# Connector.net
KiCad netlist of a schematic drawn in Altium Designer
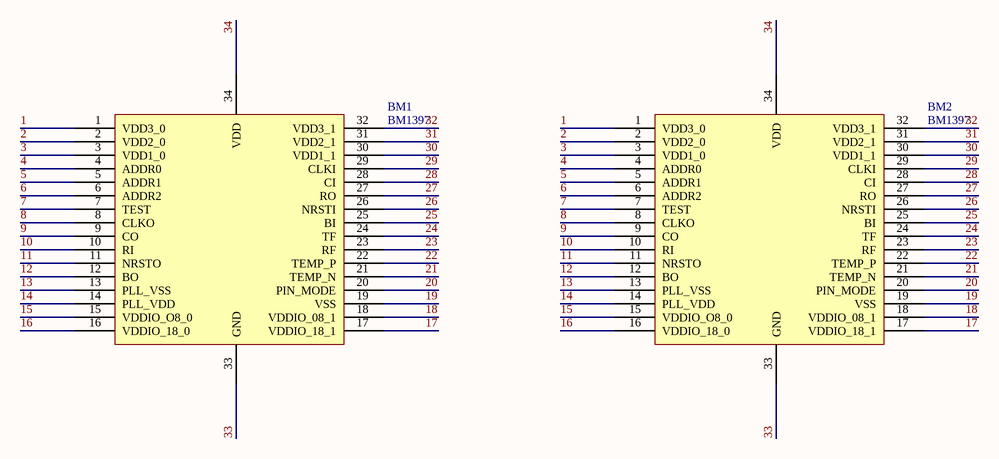
[diagram p0: Connector.SchDoc]

(export (version "E")
  (design (tool "Eeschema 10.0.6"))
  (components
    (comp (ref "BM1") (value "BM1397") (footprint "BM1387") (libsource (lib "Connector") (part "BM1397_0")))
    (comp (ref "BM2")
      (value "BM1397")
      (footprint "Connector")
      (libsource (lib "Connector") (part "BM1397_0"))
    )
  )
  (nets
    (net (code "1") (name "/1") (class "Default")
      (node (ref "BM1") (pin "1") (pinfunction "VDD3_0_1") (pintype "passive"))
      (node (ref "BM2") (pin "1") (pinfunction "VDD3_0_1") (pintype "passive"))
    )
    (net (code "2") (name "/2") (class "Default")
      (node (ref "BM1") (pin "2") (pinfunction "VDD2_0_2") (pintype "passive"))
      (node (ref "BM2") (pin "2") (pinfunction "VDD2_0_2") (pintype "passive"))
    )
    (net (code "3") (name "/3") (class "Default")
      (node (ref "BM1") (pin "3") (pinfunction "VDD1_0_3") (pintype "passive"))
      (node (ref "BM2") (pin "3") (pinfunction "VDD1_0_3") (pintype "passive"))
    )
    (net (code "4") (name "/4") (class "Default")
      (node (ref "BM1") (pin "4") (pinfunction "ADDR0_4") (pintype "passive"))
      (node (ref "BM2") (pin "4") (pinfunction "ADDR0_4") (pintype "passive"))
    )
    (net (code "5") (name "/5") (class "Default")
      (node (ref "BM1") (pin "5") (pinfunction "ADDR1_5") (pintype "passive"))
      (node (ref "BM2") (pin "5") (pinfunction "ADDR1_5") (pintype "passive"))
    )
    (net (code "6") (name "/6") (class "Default")
      (node (ref "BM1") (pin "6") (pinfunction "ADDR2_6") (pintype "passive"))
      (node (ref "BM2") (pin "6") (pinfunction "ADDR2_6") (pintype "passive"))
    )
    (net (code "7") (name "/7") (class "Default")
      (node (ref "BM1") (pin "7") (pinfunction "TEST_7") (pintype "passive"))
      (node (ref "BM2") (pin "7") (pinfunction "TEST_7") (pintype "passive"))
    )
    (net (code "8") (name "/8") (class "Default")
      (node (ref "BM1") (pin "8") (pinfunction "CLKO_8") (pintype "passive"))
      (node (ref "BM2") (pin "8") (pinfunction "CLKO_8") (pintype "passive"))
    )
    (net (code "9") (name "/9") (class "Default")
      (node (ref "BM1") (pin "9") (pinfunction "CO_9") (pintype "passive"))
      (node (ref "BM2") (pin "9") (pinfunction "CO_9") (pintype "passive"))
    )
    (net (code "10") (name "/10") (class "Default")
      (node (ref "BM1") (pin "10") (pinfunction "RI_10") (pintype "passive"))
      (node (ref "BM2") (pin "10") (pinfunction "RI_10") (pintype "passive"))
    )
    (net (code "11") (name "/11") (class "Default")
      (node (ref "BM1") (pin "11") (pinfunction "NRSTO_11") (pintype "passive"))
      (node (ref "BM2") (pin "11") (pinfunction "NRSTO_11") (pintype "passive"))
    )
    (net (code "12") (name "/12") (class "Default")
      (node (ref "BM1") (pin "12") (pinfunction "BO_12") (pintype "passive"))
      (node (ref "BM2") (pin "12") (pinfunction "BO_12") (pintype "passive"))
    )
    (net (code "13") (name "/13") (class "Default")
      (node (ref "BM1") (pin "13") (pinfunction "PLL_VSS_13") (pintype "passive"))
      (node (ref "BM2") (pin "13") (pinfunction "PLL_VSS_13") (pintype "passive"))
    )
    (net (code "14") (name "/14") (class "Default")
      (node (ref "BM1") (pin "14") (pinfunction "PLL_VDD_14") (pintype "passive"))
      (node (ref "BM2") (pin "14") (pinfunction "PLL_VDD_14") (pintype "passive"))
    )
    (net (code "15") (name "/15") (class "Default")
      (node (ref "BM1") (pin "15") (pinfunction "VDDIO_O8_0_15") (pintype "passive"))
      (node (ref "BM2") (pin "15") (pinfunction "VDDIO_O8_0_15") (pintype "passive"))
    )
    (net (code "16") (name "/16") (class "Default")
      (node (ref "BM1") (pin "16") (pinfunction "VDDIO_18_0_16") (pintype "passive"))
      (node (ref "BM2") (pin "16") (pinfunction "VDDIO_18_0_16") (pintype "passive"))
    )
    (net (code "17") (name "/17") (class "Default")
      (node (ref "BM1") (pin "17") (pinfunction "VDDIO_18_1_17") (pintype "passive"))
      (node (ref "BM2") (pin "17") (pinfunction "VDDIO_18_1_17") (pintype "passive"))
    )
    (net (code "18") (name "/18") (class "Default")
      (node (ref "BM1") (pin "18") (pinfunction "VDDIO_08_1_18") (pintype "passive"))
      (node (ref "BM2") (pin "18") (pinfunction "VDDIO_08_1_18") (pintype "passive"))
    )
    (net (code "19") (name "/19") (class "Default")
      (node (ref "BM1") (pin "19") (pinfunction "VSS_19") (pintype "passive"))
      (node (ref "BM2") (pin "19") (pinfunction "VSS_19") (pintype "passive"))
    )
    (net (code "20") (name "/20") (class "Default")
      (node (ref "BM1") (pin "20") (pinfunction "PIN_MODE_20") (pintype "passive"))
      (node (ref "BM2") (pin "20") (pinfunction "PIN_MODE_20") (pintype "passive"))
    )
    (net (code "21") (name "/21") (class "Default")
      (node (ref "BM1") (pin "21") (pinfunction "TEMP_N_21") (pintype "passive"))
      (node (ref "BM2") (pin "21") (pinfunction "TEMP_N_21") (pintype "passive"))
    )
    (net (code "22") (name "/22") (class "Default")
      (node (ref "BM1") (pin "22") (pinfunction "TEMP_P_22") (pintype "passive"))
      (node (ref "BM2") (pin "22") (pinfunction "TEMP_P_22") (pintype "passive"))
    )
    (net (code "23") (name "/23") (class "Default")
      (node (ref "BM1") (pin "23") (pinfunction "RF_23") (pintype "passive"))
      (node (ref "BM2") (pin "23") (pinfunction "RF_23") (pintype "passive"))
    )
    (net (code "24") (name "/24") (class "Default")
      (node (ref "BM1") (pin "24") (pinfunction "TF_24") (pintype "passive"))
      (node (ref "BM2") (pin "24") (pinfunction "TF_24") (pintype "passive"))
    )
    (net (code "25") (name "/25") (class "Default")
      (node (ref "BM1") (pin "25") (pinfunction "BI_25") (pintype "passive"))
      (node (ref "BM2") (pin "25") (pinfunction "BI_25") (pintype "passive"))
    )
    (net (code "26") (name "/26") (class "Default")
      (node (ref "BM1") (pin "26") (pinfunction "NRSTI_26") (pintype "passive"))
      (node (ref "BM2") (pin "26") (pinfunction "NRSTI_26") (pintype "passive"))
    )
    (net (code "27") (name "/27") (class "Default")
      (node (ref "BM1") (pin "27") (pinfunction "RO_27") (pintype "passive"))
      (node (ref "BM2") (pin "27") (pinfunction "RO_27") (pintype "passive"))
    )
    (net (code "28") (name "/28") (class "Default")
      (node (ref "BM1") (pin "28") (pinfunction "CI_28") (pintype "passive"))
      (node (ref "BM2") (pin "28") (pinfunction "CI_28") (pintype "passive"))
    )
    (net (code "29") (name "/29") (class "Default")
      (node (ref "BM1") (pin "29") (pinfunction "CLKI_29") (pintype "passive"))
      (node (ref "BM2") (pin "29") (pinfunction "CLKI_29") (pintype "passive"))
    )
    (net (code "30") (name "/30") (class "Default")
      (node (ref "BM1") (pin "30") (pinfunction "VDD1_1_30") (pintype "passive"))
      (node (ref "BM2") (pin "30") (pinfunction "VDD1_1_30") (pintype "passive"))
    )
    (net (code "31") (name "/31") (class "Default")
      (node (ref "BM1") (pin "31") (pinfunction "VDD2_1_31") (pintype "passive"))
      (node (ref "BM2") (pin "31") (pinfunction "VDD2_1_31") (pintype "passive"))
    )
    (net (code "32") (name "/32") (class "Default")
      (node (ref "BM1") (pin "32") (pinfunction "VDD3_1_32") (pintype "passive"))
      (node (ref "BM2") (pin "32") (pinfunction "VDD3_1_32") (pintype "passive"))
    )
    (net (code "33") (name "/33") (class "Default")
      (node (ref "BM1") (pin "33") (pinfunction "GND_33") (pintype "passive"))
      (node (ref "BM2") (pin "33") (pinfunction "GND_33") (pintype "passive"))
    )
    (net (code "34") (name "/34") (class "Default")
      (node (ref "BM1") (pin "34") (pinfunction "VDD_34") (pintype "passive"))
      (node (ref "BM2") (pin "34") (pinfunction "VDD_34") (pintype "passive"))
    )
  )
)
